# ESP32_Breakout.net
KiCad netlist of a schematic drawn in EAGLE
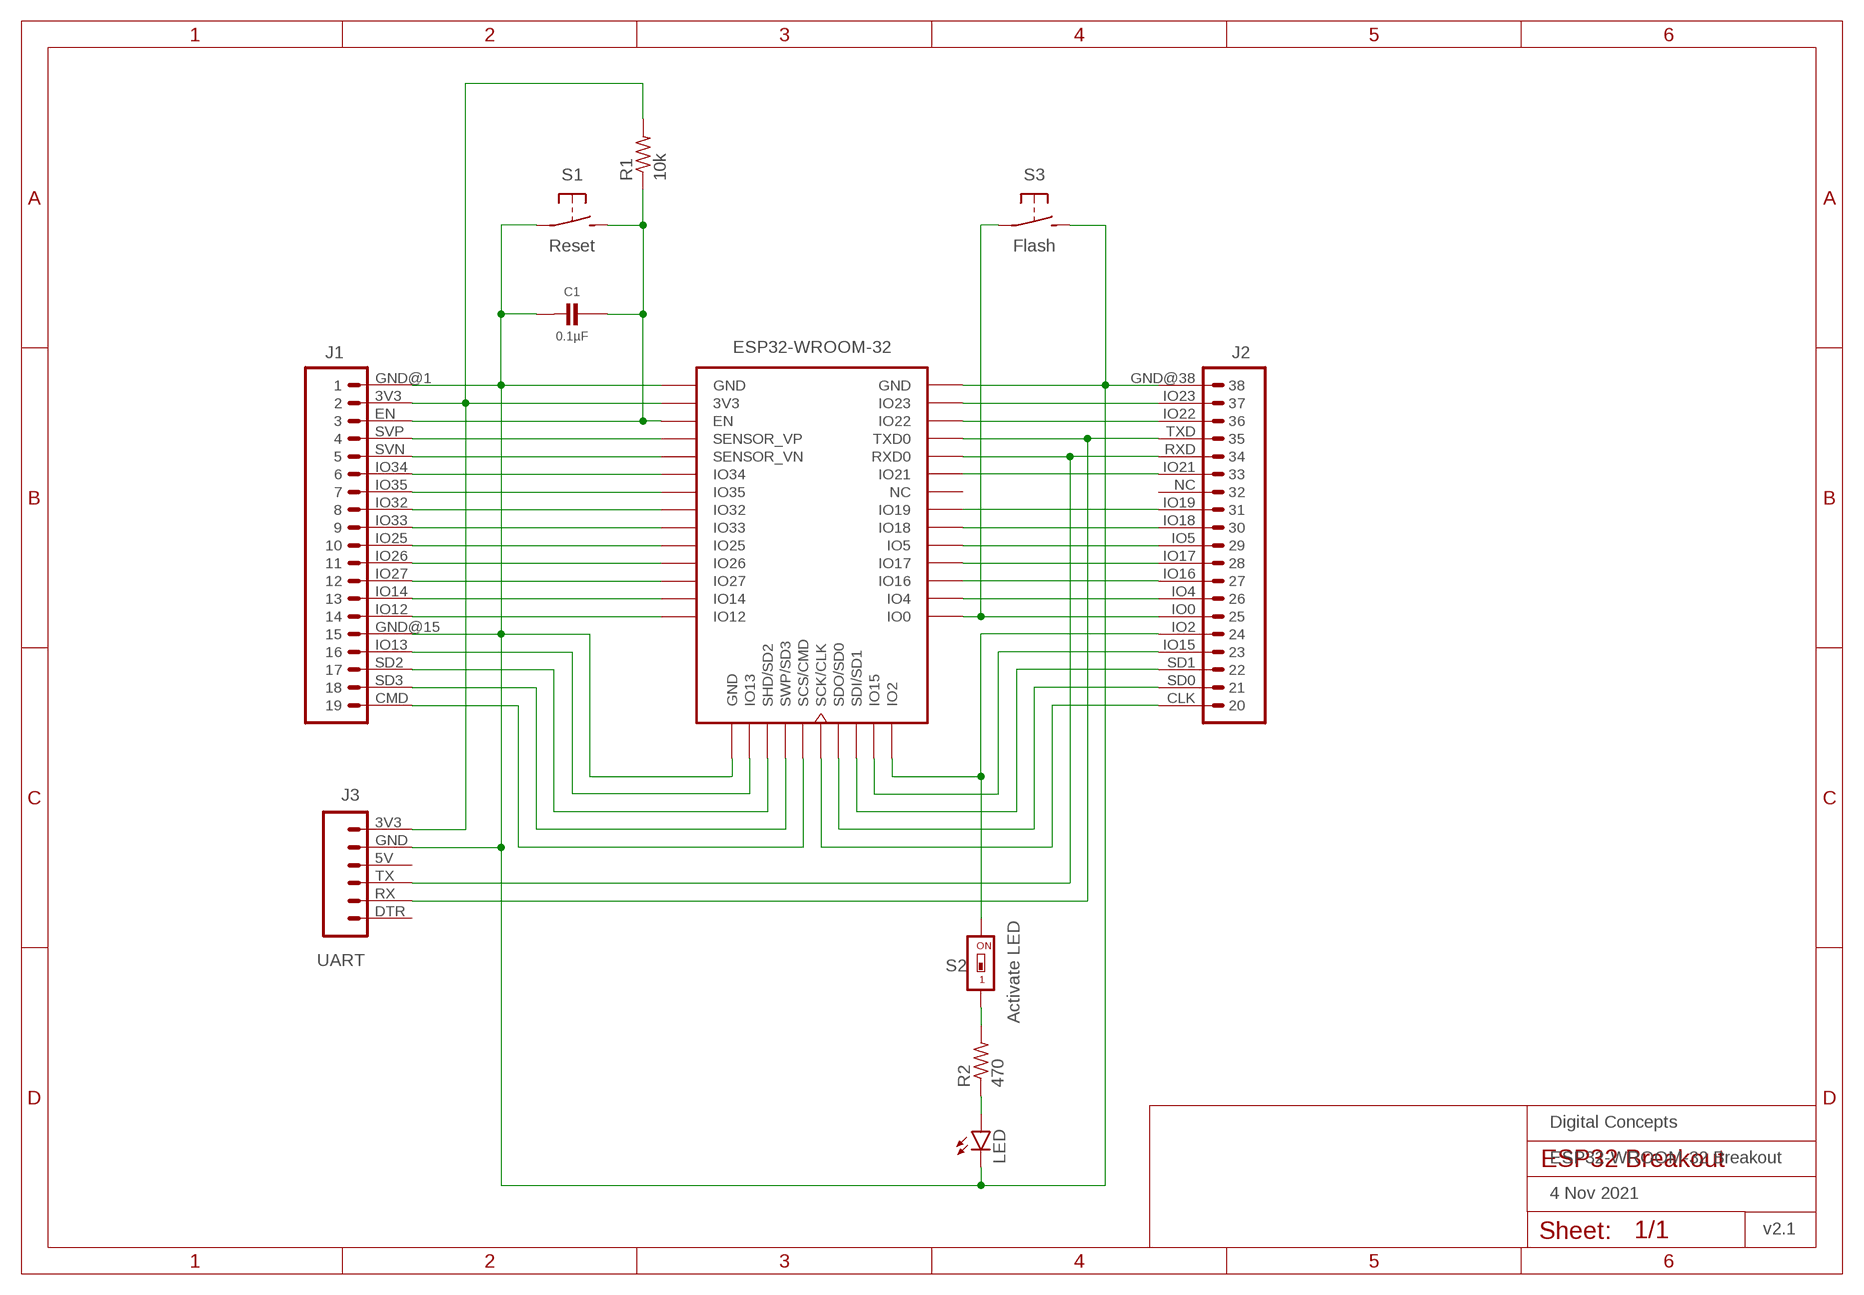
[diagram p0: schematic, sheet 1]

(export (version "E")
  (design (tool "Eeschema 10.0.6"))
  (components
    (comp (ref "C1")
      (value "0.1µF")
      (footprint "eagle-import:C0805")
      (libsource (lib "eagle-import") (part "CAPACITOR-0805"))
    )
    (comp (ref "J1")
      (value "HEADER-1X19-ESP32-L")
      (footprint "eagle-import:CONN_19-ESP32-L")
      (libsource (lib "eagle-import") (part "HEADER-1X19-ESP32-L"))
    )
    (comp (ref "J2")
      (value "HEADER-1X19-ESP32-R")
      (footprint "eagle-import:CONN_19-ESP32-R")
      (libsource (lib "eagle-import") (part "HEADER-1X19-ESP32-R"))
    )
    (comp (ref "J3")
      (value "UART")
      (footprint "eagle-import:CONN_06-UART")
      (libsource (lib "eagle-import") (part "HEADER-1X6-UART"))
    )
    (comp (ref "LED")
      (value "LEDCHIP-LED0805")
      (footprint "eagle-import:CHIP-LED0805")
      (libsource (lib "eagle-import") (part "LEDCHIP-LED0805"))
    )
    (comp (ref "R1")
      (value "10k")
      (footprint "eagle-import:R0805-VIA-2")
      (libsource (lib "eagle-import") (part "RESISTOR-VIA-2"))
    )
    (comp (ref "R2")
      (value "470")
      (footprint "eagle-import:R0805")
      (libsource (lib "eagle-import") (part "RESISTORR0805"))
    )
    (comp (ref "S1")
      (value "Reset")
      (footprint "eagle-import:SWITCH-2-PAD")
      (libsource (lib "eagle-import") (part "SWITCH-MOMENTARY-2-PIN"))
    )
    (comp (ref "S2")
      (value "Activate LED")
      (footprint "eagle-import:SMD-001")
      (libsource (lib "eagle-import") (part "SWITCH-DIP-SWS001"))
    )
    (comp (ref "S3")
      (value "Flash")
      (footprint "eagle-import:SWITCH-2-PAD")
      (libsource (lib "eagle-import") (part "SWITCH-MOMENTARY-2-PIN"))
    )
    (comp (ref "U1")
      (value "ESP32-WROOM-32")
      (footprint "eagle-import:ESP32-WROOM-32")
      (libsource (lib "eagle-import") (part "ESP32-WROOM-32-CHIP"))
    )
  )
  (nets
    (net (code "1") (name "Net-(J1-1)") (class "Default")
      (node (ref "C1") (pin "2") (pinfunction "2_2") (pintype "passive"))
      (node (ref "J1") (pin "GND@1") (pinfunction "1_GND@1") (pintype "power_in"))
      (node (ref "J1") (pin "GND@15") (pinfunction "15_GND@15") (pintype "power_in"))
      (node (ref "J2") (pin "GND@38") (pinfunction "38_GND@38") (pintype "power_in"))
      (node (ref "J3") (pin "GND") (pinfunction "5_GND") (pintype "passive"))
      (node (ref "LED") (pin "C") (pinfunction "C_C") (pintype "passive"))
      (node (ref "S1") (pin "P$1") (pinfunction "P_P$1") (pintype "passive"))
      (node (ref "S3") (pin "P$2") (pinfunction "S_P$2") (pintype "passive"))
      (node (ref "U1") (pin "GND@1") (pinfunction "GND_GND@1") (pintype "power_in"))
      (node (ref "U1") (pin "GND@15") (pinfunction "GND_GND@15") (pintype "power_in"))
      (node (ref "U1") (pin "GND@38") (pinfunction "GND_GND@38") (pintype "power_in"))
      (node (ref "U1") (pin "TP") (pinfunction "GND_TP") (pintype "power_in"))
      (node (ref "U1") (pin "TP@P1") (pinfunction "GND_TP@P1") (pintype "power_in"))
      (node (ref "U1") (pin "TP@P2") (pinfunction "GND_TP@P2") (pintype "power_in"))
      (node (ref "U1") (pin "TP@P3") (pinfunction "GND_TP@P3") (pintype "power_in"))
      (node (ref "U1") (pin "TP@P4") (pinfunction "GND_TP@P4") (pintype "power_in"))
      (node (ref "U1") (pin "TP@P5") (pinfunction "GND_TP@P5") (pintype "power_in"))
      (node (ref "U1") (pin "TP@P6") (pinfunction "GND_TP@P6") (pintype "power_in"))
      (node (ref "U1") (pin "TP@P7") (pinfunction "GND_TP@P7") (pintype "power_in"))
      (node (ref "U1") (pin "TP@P8") (pinfunction "GND_TP@P8") (pintype "power_in"))
      (node (ref "U1") (pin "TP@P9") (pinfunction "GND_TP@P9") (pintype "power_in"))
      (node (ref "U1") (pin "TP@V1") (pinfunction "GND_TP@V1") (pintype "power_in"))
      (node (ref "U1") (pin "TP@V10") (pinfunction "GND_TP@V10") (pintype "power_in"))
      (node (ref "U1") (pin "TP@V11") (pinfunction "GND_TP@V11") (pintype "power_in"))
      (node (ref "U1") (pin "TP@V12") (pinfunction "GND_TP@V12") (pintype "power_in"))
      (node (ref "U1") (pin "TP@V2") (pinfunction "GND_TP@V2") (pintype "power_in"))
      (node (ref "U1") (pin "TP@V3") (pinfunction "GND_TP@V3") (pintype "power_in"))
      (node (ref "U1") (pin "TP@V4") (pinfunction "GND_TP@V4") (pintype "power_in"))
      (node (ref "U1") (pin "TP@V5") (pinfunction "GND_TP@V5") (pintype "power_in"))
      (node (ref "U1") (pin "TP@V6") (pinfunction "GND_TP@V6") (pintype "power_in"))
      (node (ref "U1") (pin "TP@V7") (pinfunction "GND_TP@V7") (pintype "power_in"))
      (node (ref "U1") (pin "TP@V8") (pinfunction "GND_TP@V8") (pintype "power_in"))
      (node (ref "U1") (pin "TP@V9") (pinfunction "GND_TP@V9") (pintype "power_in"))
      (node (ref "U1") (pin "TP@VP5") (pinfunction "GND_TP@VP5") (pintype "power_in"))
    )
    (net (code "2") (name "Net-(J1-2)") (class "Default")
      (node (ref "J1") (pin "3V3") (pinfunction "2_3V3") (pintype "power_in"))
      (node (ref "J3") (pin "3V3") (pinfunction "6_3V3") (pintype "passive"))
      (node (ref "R1") (pin "2") (pinfunction "2_2") (pintype "passive"))
      (node (ref "R1") (pin "2@VIA") (pinfunction "2_2@VIA") (pintype "passive"))
      (node (ref "U1") (pin "3V3") (pinfunction "3V3_3V3") (pintype "power_in"))
    )
    (net (code "3") (name "Net-(J1-3)") (class "Default")
      (node (ref "C1") (pin "1") (pinfunction "1_1") (pintype "passive"))
      (node (ref "J1") (pin "EN") (pinfunction "3_EN") (pintype "input"))
      (node (ref "R1") (pin "1") (pinfunction "1_1") (pintype "passive"))
      (node (ref "S1") (pin "P$2") (pinfunction "S_P$2") (pintype "passive"))
      (node (ref "U1") (pin "EN") (pinfunction "EN_EN") (pintype "input"))
    )
    (net (code "4") (name "Net-(J1-4)") (class "Default")
      (node (ref "J1") (pin "SVP") (pinfunction "4_SVP") (pintype "input"))
      (node (ref "U1") (pin "SENSOR_VP") (pinfunction "SENSOR_VP_SENSOR_VP") (pintype "input"))
    )
    (net (code "5") (name "Net-(J1-5)") (class "Default")
      (node (ref "J1") (pin "SVN") (pinfunction "5_SVN") (pintype "input"))
      (node (ref "U1") (pin "SENSOR_VN") (pinfunction "SENSOR_VN_SENSOR_VN") (pintype "input"))
    )
    (net (code "6") (name "Net-(J1-6)") (class "Default")
      (node (ref "J1") (pin "IO34") (pinfunction "6_IO34") (pintype "input"))
      (node (ref "U1") (pin "IO34") (pinfunction "IO34_IO34") (pintype "input"))
    )
    (net (code "7") (name "Net-(J1-7)") (class "Default")
      (node (ref "J1") (pin "IO35") (pinfunction "7_IO35") (pintype "input"))
      (node (ref "U1") (pin "IO35") (pinfunction "IO35_IO35") (pintype "input"))
    )
    (net (code "8") (name "Net-(J1-8)") (class "Default")
      (node (ref "J1") (pin "IO32") (pinfunction "8_IO32") (pintype "bidirectional"))
      (node (ref "U1") (pin "IO32") (pinfunction "IO32_IO32") (pintype "bidirectional"))
    )
    (net (code "9") (name "Net-(J1-9)") (class "Default")
      (node (ref "J1") (pin "IO33") (pinfunction "9_IO33") (pintype "bidirectional"))
      (node (ref "U1") (pin "IO33") (pinfunction "IO33_IO33") (pintype "bidirectional"))
    )
    (net (code "10") (name "Net-(J1-10)") (class "Default")
      (node (ref "J1") (pin "IO25") (pinfunction "10_IO25") (pintype "bidirectional"))
      (node (ref "U1") (pin "IO25") (pinfunction "IO25_IO25") (pintype "bidirectional"))
    )
    (net (code "11") (name "Net-(J1-11)") (class "Default")
      (node (ref "J1") (pin "IO26") (pinfunction "11_IO26") (pintype "bidirectional"))
      (node (ref "U1") (pin "IO26") (pinfunction "IO26_IO26") (pintype "bidirectional"))
    )
    (net (code "12") (name "Net-(J1-12)") (class "Default")
      (node (ref "J1") (pin "IO27") (pinfunction "12_IO27") (pintype "bidirectional"))
      (node (ref "U1") (pin "IO27") (pinfunction "IO27_IO27") (pintype "bidirectional"))
    )
    (net (code "13") (name "Net-(J1-13)") (class "Default")
      (node (ref "J1") (pin "IO14") (pinfunction "13_IO14") (pintype "bidirectional"))
      (node (ref "U1") (pin "IO14") (pinfunction "IO14_IO14") (pintype "bidirectional"))
    )
    (net (code "14") (name "Net-(J1-14)") (class "Default")
      (node (ref "J1") (pin "IO12") (pinfunction "14_IO12") (pintype "bidirectional"))
      (node (ref "U1") (pin "IO12") (pinfunction "IO12_IO12") (pintype "bidirectional"))
    )
    (net (code "15") (name "Net-(J1-16)") (class "Default")
      (node (ref "J1") (pin "IO13") (pinfunction "16_IO13") (pintype "bidirectional"))
      (node (ref "U1") (pin "IO13") (pinfunction "IO13_IO13") (pintype "bidirectional"))
    )
    (net (code "16") (name "Net-(J1-17)") (class "Default")
      (node (ref "J1") (pin "SD2") (pinfunction "17_SD2") (pintype "bidirectional"))
      (node (ref "U1") (pin "SD2") (pinfunction "SHD/SD2_SD2") (pintype "bidirectional"))
    )
    (net (code "17") (name "Net-(J1-18)") (class "Default")
      (node (ref "J1") (pin "SD3") (pinfunction "18_SD3") (pintype "bidirectional"))
      (node (ref "U1") (pin "SD3") (pinfunction "SWP/SD3_SD3") (pintype "bidirectional"))
    )
    (net (code "18") (name "Net-(J1-19)") (class "Default")
      (node (ref "J1") (pin "CMD") (pinfunction "19_CMD") (pintype "bidirectional"))
      (node (ref "U1") (pin "CMD") (pinfunction "SCS/CMD_CMD") (pintype "bidirectional"))
    )
    (net (code "19") (name "Net-(J2-20)") (class "Default")
      (node (ref "J2") (pin "CLK") (pinfunction "20_CLK") (pintype "bidirectional"))
      (node (ref "U1") (pin "CLK") (pinfunction "SCK/CLK_CLK") (pintype "bidirectional"))
    )
    (net (code "20") (name "Net-(J2-21)") (class "Default")
      (node (ref "J2") (pin "SD0") (pinfunction "21_SD0") (pintype "bidirectional"))
      (node (ref "U1") (pin "SD0") (pinfunction "SDO/SD0_SD0") (pintype "bidirectional"))
    )
    (net (code "21") (name "Net-(J2-22)") (class "Default")
      (node (ref "J2") (pin "SD1") (pinfunction "22_SD1") (pintype "bidirectional"))
      (node (ref "U1") (pin "SD1") (pinfunction "SDI/SD1_SD1") (pintype "bidirectional"))
    )
    (net (code "22") (name "Net-(J2-23)") (class "Default")
      (node (ref "J2") (pin "IO15") (pinfunction "23_IO15") (pintype "bidirectional"))
      (node (ref "U1") (pin "IO15") (pinfunction "IO15_IO15") (pintype "bidirectional"))
    )
    (net (code "23") (name "Net-(J2-24)") (class "Default")
      (node (ref "J2") (pin "IO2") (pinfunction "24_IO2") (pintype "bidirectional"))
      (node (ref "S2") (pin "2") (pinfunction "2_2") (pintype "passive"))
      (node (ref "U1") (pin "IO2") (pinfunction "IO2_IO2") (pintype "bidirectional"))
    )
    (net (code "24") (name "Net-(J2-25)") (class "Default")
      (node (ref "J2") (pin "IO0") (pinfunction "25_IO0") (pintype "bidirectional"))
      (node (ref "S3") (pin "P$1") (pinfunction "P_P$1") (pintype "passive"))
      (node (ref "U1") (pin "IO0") (pinfunction "IO0_IO0") (pintype "bidirectional"))
    )
    (net (code "25") (name "Net-(J2-26)") (class "Default")
      (node (ref "J2") (pin "IO4") (pinfunction "26_IO4") (pintype "bidirectional"))
      (node (ref "U1") (pin "IO4") (pinfunction "IO4_IO4") (pintype "bidirectional"))
    )
    (net (code "26") (name "Net-(J2-27)") (class "Default")
      (node (ref "J2") (pin "IO16") (pinfunction "27_IO16") (pintype "bidirectional"))
      (node (ref "U1") (pin "IO16") (pinfunction "IO16_IO16") (pintype "bidirectional"))
    )
    (net (code "27") (name "Net-(J2-28)") (class "Default")
      (node (ref "J2") (pin "IO17") (pinfunction "28_IO17") (pintype "bidirectional"))
      (node (ref "U1") (pin "IO17") (pinfunction "IO17_IO17") (pintype "bidirectional"))
    )
    (net (code "28") (name "Net-(J2-29)") (class "Default")
      (node (ref "J2") (pin "IO5") (pinfunction "29_IO5") (pintype "bidirectional"))
      (node (ref "U1") (pin "IO5") (pinfunction "IO5_IO5") (pintype "bidirectional"))
    )
    (net (code "29") (name "Net-(J2-30)") (class "Default")
      (node (ref "J2") (pin "IO18") (pinfunction "30_IO18") (pintype "bidirectional"))
      (node (ref "U1") (pin "IO18") (pinfunction "IO18_IO18") (pintype "bidirectional"))
    )
    (net (code "30") (name "Net-(J2-31)") (class "Default")
      (node (ref "J2") (pin "IO19") (pinfunction "31_IO19") (pintype "bidirectional"))
      (node (ref "U1") (pin "IO19") (pinfunction "IO19_IO19") (pintype "bidirectional"))
    )
    (net (code "31") (name "Net-(J2-33)") (class "Default")
      (node (ref "J2") (pin "IO21") (pinfunction "33_IO21") (pintype "bidirectional"))
      (node (ref "U1") (pin "IO21") (pinfunction "IO21_IO21") (pintype "bidirectional"))
    )
    (net (code "32") (name "Net-(J2-34)") (class "Default")
      (node (ref "J2") (pin "RXD") (pinfunction "34_RXD") (pintype "bidirectional"))
      (node (ref "J3") (pin "TX") (pinfunction "3_TX") (pintype "passive"))
      (node (ref "U1") (pin "RXD0") (pinfunction "RXD0_RXD0") (pintype "bidirectional"))
    )
    (net (code "33") (name "Net-(J2-35)") (class "Default")
      (node (ref "J2") (pin "TXD") (pinfunction "35_TXD") (pintype "bidirectional"))
      (node (ref "J3") (pin "RX") (pinfunction "2_RX") (pintype "passive"))
      (node (ref "U1") (pin "TXD0") (pinfunction "TXD0_TXD0") (pintype "bidirectional"))
    )
    (net (code "34") (name "Net-(J2-36)") (class "Default")
      (node (ref "J2") (pin "IO22") (pinfunction "36_IO22") (pintype "bidirectional"))
      (node (ref "U1") (pin "IO22") (pinfunction "IO22_IO22") (pintype "bidirectional"))
    )
    (net (code "35") (name "Net-(J2-37)") (class "Default")
      (node (ref "J2") (pin "IO23") (pinfunction "37_IO23") (pintype "bidirectional"))
      (node (ref "U1") (pin "IO23") (pinfunction "IO23_IO23") (pintype "bidirectional"))
    )
    (net (code "36") (name "Net-(LED-PadA)") (class "Default")
      (node (ref "LED") (pin "A") (pinfunction "A_A") (pintype "passive"))
      (node (ref "R2") (pin "1") (pinfunction "1_1") (pintype "passive"))
    )
    (net (code "37") (name "Net-(R2-Pad2)") (class "Default")
      (node (ref "R2") (pin "2") (pinfunction "2_2") (pintype "passive"))
      (node (ref "S2") (pin "1") (pinfunction "1_1") (pintype "passive"))
    )
    (net (code "38") (name "unconnected-(J2-32-PadNC)") (class "Default")
      (node (ref "J2") (pin "NC") (pinfunction "32_NC") (pintype "no_connect"))
    )
    (net (code "39") (name "unconnected-(J3-1-PadDTR)") (class "Default")
      (node (ref "J3") (pin "DTR") (pinfunction "1_DTR") (pintype "passive"))
    )
    (net (code "40") (name "unconnected-(J3-4-Pad5V)") (class "Default")
      (node (ref "J3") (pin "5V") (pinfunction "4_5V") (pintype "passive"))
    )
    (net (code "41") (name "unconnected-(U1-PadNC)") (class "Default")
      (node (ref "U1") (pin "NC") (pinfunction "NC_NC") (pintype "no_connect"))
    )
  )
)
